# source_eagle.net
KiCad netlist of a schematic drawn in EAGLE
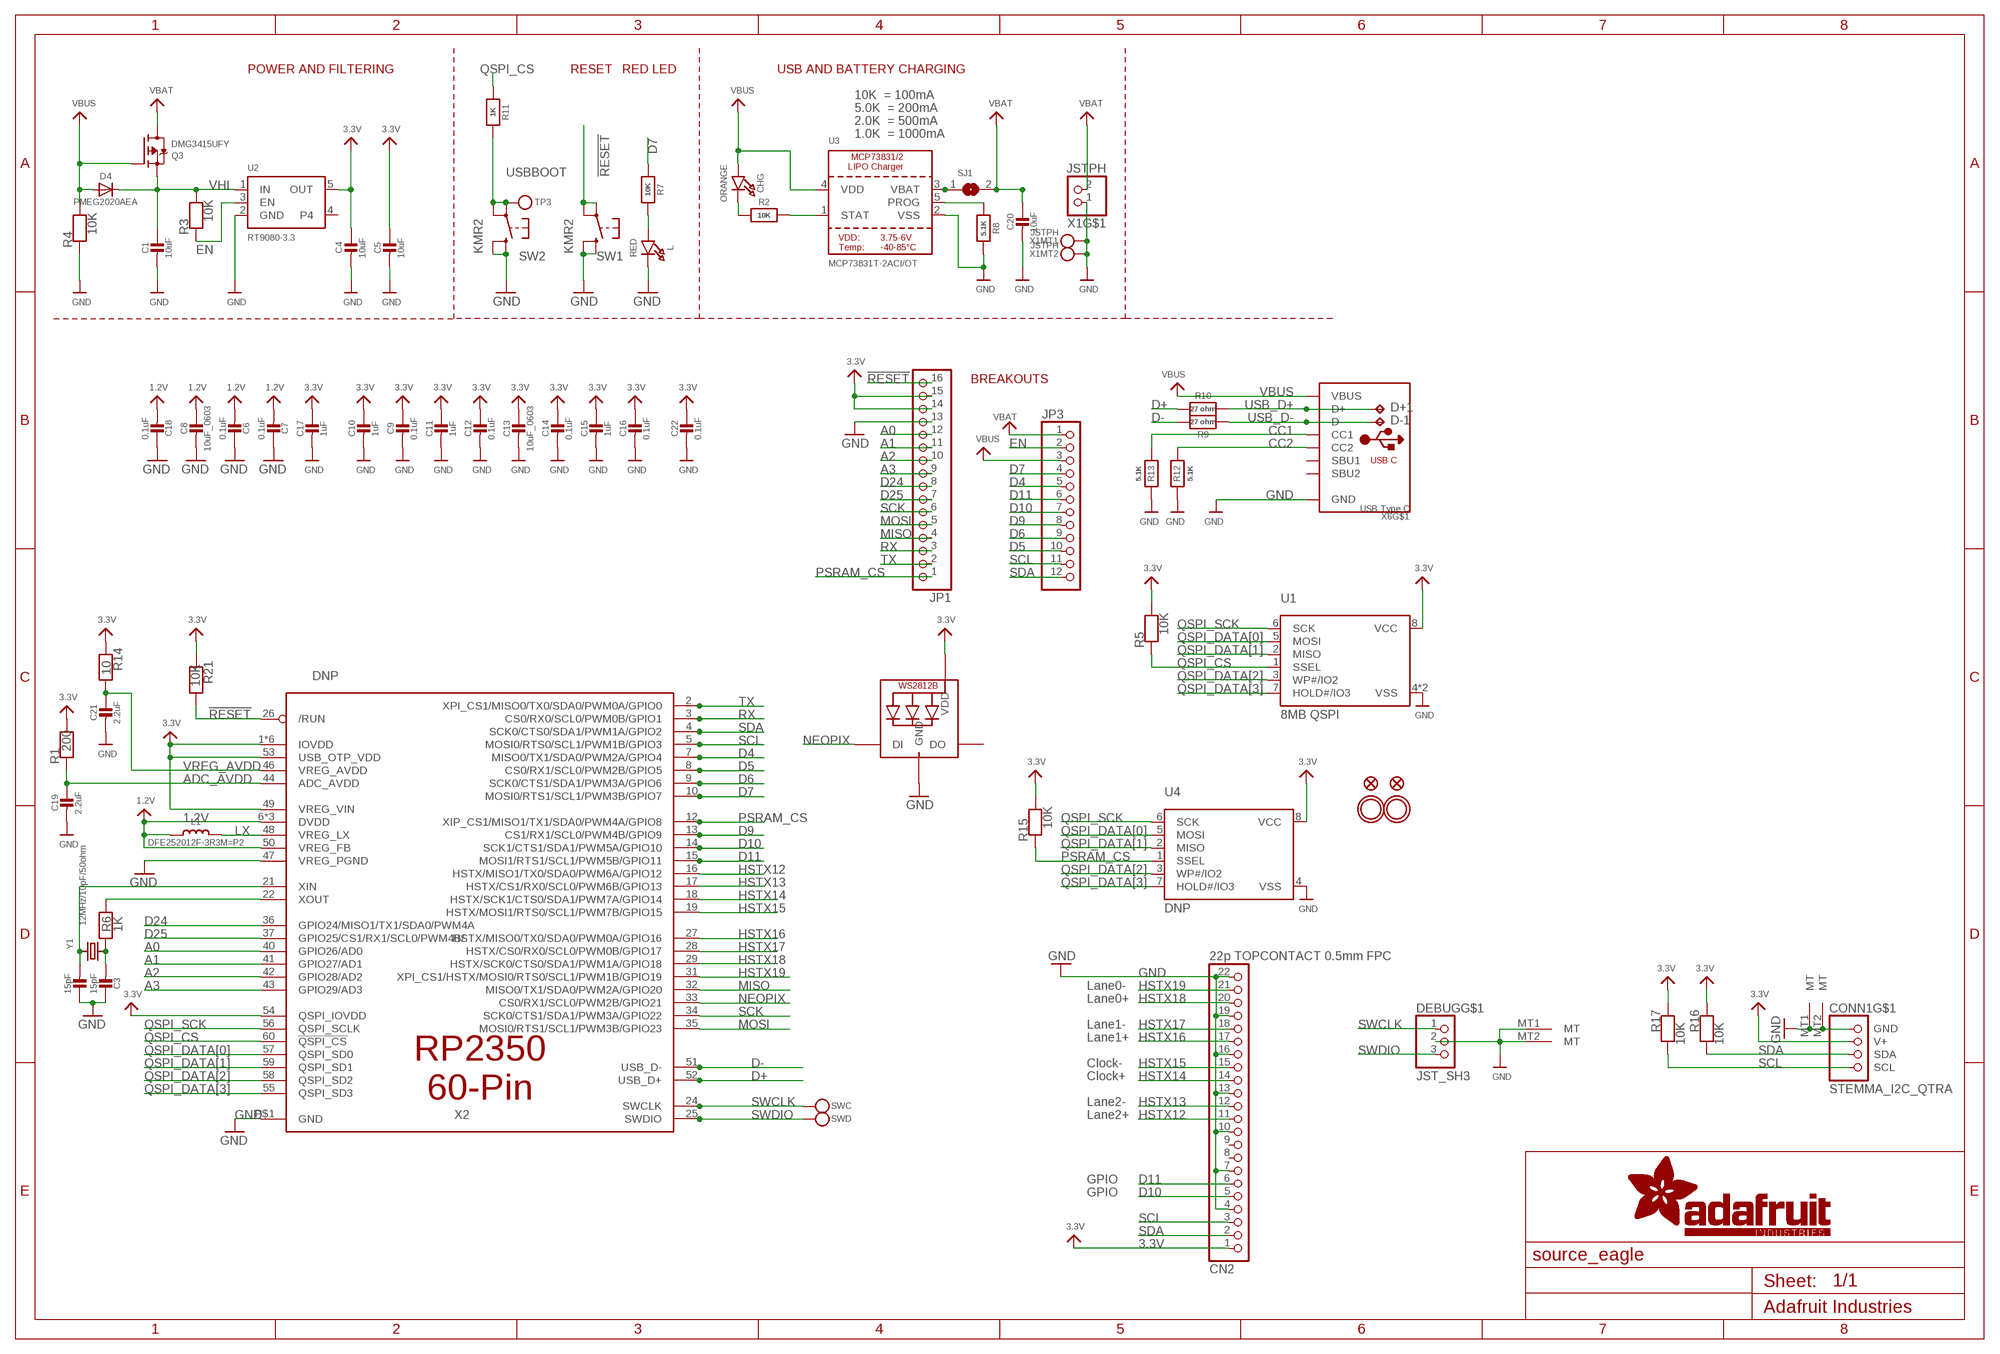
[diagram p0: schematic, sheet 1]

(export (version "E")
  (design (tool "Eeschema 10.0.6"))
  (components
    (comp (ref "C1")
      (value "10uF")
      (footprint "eagle-import:0805-NO")
      (libsource (lib "eagle-import") (part "CAP_CERAMIC0805-NOOUTLINE"))
    )
    (comp (ref "C2")
      (value "15pF")
      (footprint "eagle-import:_0402NO")
      (libsource (lib "eagle-import") (part "CAP_CERAMIC_0402NO"))
    )
    (comp (ref "C3")
      (value "15pF")
      (footprint "eagle-import:_0402NO")
      (libsource (lib "eagle-import") (part "CAP_CERAMIC_0402NO"))
    )
    (comp (ref "C4")
      (value "10uF")
      (footprint "eagle-import:0805-NO")
      (fields (field (name "REV") "B"))
      (libsource (lib "eagle-import") (part "CAP_CERAMIC0805-NOOUTLINE"))
    )
    (comp (ref "C5")
      (value "10uF")
      (footprint "eagle-import:0603-NO")
      (libsource (lib "eagle-import") (part "CAP_CERAMIC0603_NO"))
    )
    (comp (ref "C6")
      (value "0.1uF")
      (footprint "eagle-import:_0402NO")
      (libsource (lib "eagle-import") (part "CAP_CERAMIC_0402NO"))
    )
    (comp (ref "C7")
      (value "0.1uF")
      (footprint "eagle-import:_0402NO")
      (libsource (lib "eagle-import") (part "CAP_CERAMIC_0402NO"))
    )
    (comp (ref "C8")
      (value "10uF_0603")
      (footprint "eagle-import:_0603MP")
      (libsource (lib "eagle-import") (part "CAP_CERAMIC_0603MP"))
    )
    (comp (ref "C9")
      (value "0.1uF")
      (footprint "eagle-import:_0402NO")
      (libsource (lib "eagle-import") (part "CAP_CERAMIC_0402NO"))
    )
    (comp (ref "C10")
      (value "1uF")
      (footprint "eagle-import:_0402NO")
      (libsource (lib "eagle-import") (part "CAP_CERAMIC_0402NO"))
    )
    (comp (ref "C11")
      (value "1uF")
      (footprint "eagle-import:_0402NO")
      (libsource (lib "eagle-import") (part "CAP_CERAMIC_0402NO"))
    )
    (comp (ref "C12")
      (value "0.1uF")
      (footprint "eagle-import:_0402NO")
      (libsource (lib "eagle-import") (part "CAP_CERAMIC_0402NO"))
    )
    (comp (ref "C13")
      (value "10uF_0603")
      (footprint "eagle-import:_0603MP")
      (libsource (lib "eagle-import") (part "CAP_CERAMIC_0603MP"))
    )
    (comp (ref "C14")
      (value "0.1uF")
      (footprint "eagle-import:_0402NO")
      (libsource (lib "eagle-import") (part "CAP_CERAMIC_0402NO"))
    )
    (comp (ref "C15")
      (value "1uF")
      (footprint "eagle-import:_0402NO")
      (libsource (lib "eagle-import") (part "CAP_CERAMIC_0402NO"))
    )
    (comp (ref "C16")
      (value "0.1uF")
      (footprint "eagle-import:_0402NO")
      (libsource (lib "eagle-import") (part "CAP_CERAMIC_0402NO"))
    )
    (comp (ref "C17")
      (value "1uF")
      (footprint "eagle-import:_0402NO")
      (libsource (lib "eagle-import") (part "CAP_CERAMIC_0402NO"))
    )
    (comp (ref "C18")
      (value "0.1uF")
      (footprint "eagle-import:_0402NO")
      (libsource (lib "eagle-import") (part "CAP_CERAMIC_0402NO"))
    )
    (comp (ref "C19")
      (value "2.2uF")
      (footprint "eagle-import:_0402NO")
      (libsource (lib "eagle-import") (part "CAP_CERAMIC_0402NO"))
    )
    (comp (ref "C20")
      (value "10uF")
      (footprint "eagle-import:0805-NO")
      (libsource (lib "eagle-import") (part "CAP_CERAMIC0805-NOOUTLINE"))
    )
    (comp (ref "C21")
      (value "2.2uF")
      (footprint "eagle-import:_0402NO")
      (libsource (lib "eagle-import") (part "CAP_CERAMIC_0402NO"))
    )
    (comp (ref "C22")
      (value "0.1uF")
      (footprint "eagle-import:_0402NO")
      (libsource (lib "eagle-import") (part "CAP_CERAMIC_0402NO"))
    )
    (comp (ref "CHG")
      (value "ORANGE")
      (footprint "eagle-import:CHIPLED_0603_NOOUTLINE")
      (libsource (lib "eagle-import") (part "LED0603_NOOUTLINE"))
    )
    (comp (ref "CN2")
      (value "22p TOPCONTACT 0.5mm FPC")
      (footprint "eagle-import:FPC_22PIN")
      (libsource (lib "eagle-import") (part "HEADER-1X22_22PIN_0.5MM_BOT"))
    )
    (comp (ref "CONN1")
      (value "STEMMA_I2C_QTRA")
      (footprint "eagle-import:JST_SH4_RA")
      (libsource (lib "eagle-import") (part "STEMMA_I2C_QTRA"))
    )
    (comp (ref "D+1")
      (value "TPB1,27")
      (footprint "eagle-import:B1,27")
      (libsource (lib "eagle-import") (part "TPB1,27"))
    )
    (comp (ref "D-1")
      (value "TPB1,27")
      (footprint "eagle-import:B1,27")
      (libsource (lib "eagle-import") (part "TPB1,27"))
    )
    (comp (ref "D4")
      (value "PMEG2020AEA")
      (footprint "eagle-import:SOD-323F")
      (libsource (lib "eagle-import") (part "DIODESOD-323F"))
    )
    (comp (ref "DEBUG")
      (value "JST_SH3")
      (footprint "eagle-import:JST_SH3_RA")
      (libsource (lib "eagle-import") (part "CON_JST_SH_3PINVERT"))
    )
    (comp (ref "JP1")
      (value "HEADER-1X16ROUND")
      (footprint "eagle-import:1X16_ROUND")
      (libsource (lib "eagle-import") (part "HEADER-1X16ROUND"))
    )
    (comp (ref "JP3")
      (value "HEADER-1X12")
      (footprint "eagle-import:1X12_ROUND")
      (libsource (lib "eagle-import") (part "HEADER-1X12"))
    )
    (comp (ref "L")
      (value "RED")
      (footprint "eagle-import:CHIPLED_0603_NOOUTLINE")
      (libsource (lib "eagle-import") (part "LED0603_NOOUTLINE"))
    )
    (comp (ref "L1")
      (value "DFE252012F-3R3M=P2")
      (footprint "eagle-import:INDUCTOR_1007")
      (libsource (lib "eagle-import") (part "INDUCTOR"))
    )
    (comp (ref "LED1")
      (value "WS2812B_SK6805_1515")
      (footprint "eagle-import:SK6805_1515")
      (libsource (lib "eagle-import") (part "WS2812B_SK6805_1515"))
    )
    (comp (ref "Q3")
      (value "DMG3415UFY")
      (footprint "eagle-import:DFN2015-3")
      (libsource (lib "eagle-import") (part "MOSFET-P_DFN2015"))
    )
    (comp (ref "R1")
      (value "200")
      (footprint "eagle-import:_0402NO")
      (libsource (lib "eagle-import") (part "RESISTOR_0402NO"))
    )
    (comp (ref "R2")
      (value "10K")
      (footprint "eagle-import:_0402NO")
      (libsource (lib "eagle-import") (part "RESISTOR_0402NO"))
    )
    (comp (ref "R3")
      (value "10K")
      (footprint "eagle-import:_0402NO")
      (libsource (lib "eagle-import") (part "RESISTOR_0402NO"))
    )
    (comp (ref "R4")
      (value "10K")
      (footprint "eagle-import:_0402NO")
      (libsource (lib "eagle-import") (part "RESISTOR_0402NO"))
    )
    (comp (ref "R5")
      (value "10K")
      (footprint "eagle-import:_0402NO")
      (libsource (lib "eagle-import") (part "RESISTOR_0402NO"))
    )
    (comp (ref "R6")
      (value "1K")
      (footprint "eagle-import:_0402NO")
      (libsource (lib "eagle-import") (part "RESISTOR_0402NO"))
    )
    (comp (ref "R7")
      (value "10K")
      (footprint "eagle-import:_0402NO")
      (libsource (lib "eagle-import") (part "RESISTOR_0402NO"))
    )
    (comp (ref "R8")
      (value "5.1K")
      (footprint "eagle-import:_0402NO")
      (libsource (lib "eagle-import") (part "RESISTOR_0402NO"))
    )
    (comp (ref "R9")
      (value "27 ohm")
      (footprint "eagle-import:_0402NO")
      (libsource (lib "eagle-import") (part "RESISTOR_0402NO"))
    )
    (comp (ref "R10")
      (value "27 ohm")
      (footprint "eagle-import:_0402NO")
      (libsource (lib "eagle-import") (part "RESISTOR_0402NO"))
    )
    (comp (ref "R11")
      (value "1K")
      (footprint "eagle-import:_0402NO")
      (libsource (lib "eagle-import") (part "RESISTOR_0402NO"))
    )
    (comp (ref "R12")
      (value "5.1K")
      (footprint "eagle-import:_0402NO")
      (libsource (lib "eagle-import") (part "RESISTOR_0402NO"))
    )
    (comp (ref "R13")
      (value "5.1K")
      (footprint "eagle-import:_0402NO")
      (libsource (lib "eagle-import") (part "RESISTOR_0402NO"))
    )
    (comp (ref "R14")
      (value "10")
      (footprint "eagle-import:_0402NO")
      (libsource (lib "eagle-import") (part "RESISTOR_0402NO"))
    )
    (comp (ref "R15")
      (value "10K")
      (footprint "eagle-import:_0402NO")
      (libsource (lib "eagle-import") (part "RESISTOR_0402NO"))
    )
    (comp (ref "R16")
      (value "10K")
      (footprint "eagle-import:_0402NO")
      (libsource (lib "eagle-import") (part "RESISTOR_0402NO"))
    )
    (comp (ref "R17")
      (value "10K")
      (footprint "eagle-import:_0402NO")
      (libsource (lib "eagle-import") (part "RESISTOR_0402NO"))
    )
    (comp (ref "R21")
      (value "10K")
      (footprint "eagle-import:_0402NO")
      (libsource (lib "eagle-import") (part "RESISTOR_0402NO"))
    )
    (comp (ref "SJ1")
      (value "SOLDERJUMPERCLOSED")
      (footprint "eagle-import:SOLDERJUMPER_CLOSEDWIRE")
      (libsource (lib "eagle-import") (part "SOLDERJUMPERCLOSED"))
    )
    (comp (ref "SW1")
      (value "KMR2")
      (footprint "eagle-import:BTN_RKB2_4.6X2.8")
      (libsource (lib "eagle-import") (part "SWITCH_TACT_SMT_RKB2"))
    )
    (comp (ref "SW2")
      (value "KMR2")
      (footprint "eagle-import:BTN_RKB2_4.6X2.8")
      (libsource (lib "eagle-import") (part "SWITCH_TACT_SMT_RKB2"))
    )
    (comp (ref "SWC")
      (value "TESTPOINTROUND1MM")
      (footprint "eagle-import:TESTPOINT_ROUND_1MM")
      (libsource (lib "eagle-import") (part "TESTPOINTROUND1MM"))
    )
    (comp (ref "SWD")
      (value "TESTPOINTROUND1MM")
      (footprint "eagle-import:TESTPOINT_ROUND_1MM")
      (libsource (lib "eagle-import") (part "TESTPOINTROUND1MM"))
    )
    (comp (ref "TP3")
      (value "TESTPOINTROUND1.5MMNO")
      (footprint "eagle-import:TESTPOINT_ROUND_1.5MM_NO")
      (libsource (lib "eagle-import") (part "TESTPOINTROUND1.5MMNO"))
    )
    (comp (ref "U$31")
      (value "MOUNTINGHOLE2.5")
      (footprint "eagle-import:MOUNTINGHOLE_2.5_PLATED")
      (libsource (lib "eagle-import") (part "MOUNTINGHOLE2.5"))
    )
    (comp (ref "U$32")
      (value "MOUNTINGHOLE2.5")
      (footprint "eagle-import:MOUNTINGHOLE_2.5_PLATED")
      (libsource (lib "eagle-import") (part "MOUNTINGHOLE2.5"))
    )
    (comp (ref "U$34")
      (value "FIDUCIAL_1MM")
      (footprint "eagle-import:FIDUCIAL_1MM")
      (libsource (lib "eagle-import") (part "FIDUCIAL_1MM"))
    )
    (comp (ref "U$35")
      (value "FIDUCIAL_1MM")
      (footprint "eagle-import:FIDUCIAL_1MM")
      (libsource (lib "eagle-import") (part "FIDUCIAL_1MM"))
    )
    (comp (ref "U1")
      (value "8MB QSPI")
      (footprint "eagle-import:USON8_4X4")
      (libsource (lib "eagle-import") (part "SPIFLASH_8PIN_4X4"))
    )
    (comp (ref "U2")
      (value "RT9080-3.3")
      (footprint "eagle-import:SOT23-5")
      (fields (field (name "JLC_ROTATION") "0"))
      (libsource (lib "eagle-import") (part "VREG_SOT23-5"))
    )
    (comp (ref "U3")
      (value "MCP73831T-2ACI/OT")
      (footprint "eagle-import:SOT23-5")
      (libsource (lib "eagle-import") (part "MCP73831/2"))
    )
    (comp (ref "U4")
      (value "DNP")
      (footprint "eagle-import:SOIC8_150MIL")
      (libsource (lib "eagle-import") (part "SPIFLASH_8PIN"))
    )
    (comp (ref "X1")
      (value "JSTPH")
      (footprint "eagle-import:JSTPH2_BATT")
      (libsource (lib "eagle-import") (part "CON_JST_PH_2PIN_MT_BATT"))
    )
    (comp (ref "X2")
      (value "DNP")
      (footprint "eagle-import:QFN60_7MM_REDUCEDEPAD")
      (libsource (lib "eagle-import") (part "RP2350_QFN60"))
    )
    (comp (ref "X6")
      (value "USB Type C")
      (footprint "eagle-import:USB_C_CUSB31-CFM2AX-01-X")
      (libsource (lib "eagle-import") (part "USB_C"))
    )
    (comp (ref "Y1")
      (value "12MHz/10pF/50ohm")
      (footprint "eagle-import:CRYSTAL_2.5X2")
      (libsource (lib "eagle-import") (part "CRYSTAL2.5X2.0"))
    )
  )
  (nets
    (net (code "1") (name "/A0") (class "Default")
      (node (ref "JP1") (pin "12") (pinfunction "12_12") (pintype "passive"))
      (node (ref "X2") (pin "40") (pinfunction "GPIO26/AD0_40") (pintype "bidirectional"))
    )
    (net (code "2") (name "/A1") (class "Default")
      (node (ref "JP1") (pin "11") (pinfunction "11_11") (pintype "passive"))
      (node (ref "X2") (pin "41") (pinfunction "GPIO27/AD1_41") (pintype "bidirectional"))
    )
    (net (code "3") (name "/A2") (class "Default")
      (node (ref "JP1") (pin "10") (pinfunction "10_10") (pintype "passive"))
      (node (ref "X2") (pin "42") (pinfunction "GPIO28/AD2_42") (pintype "bidirectional"))
    )
    (net (code "4") (name "/A3") (class "Default")
      (node (ref "JP1") (pin "9") (pinfunction "9_9") (pintype "passive"))
      (node (ref "X2") (pin "43") (pinfunction "GPIO29/AD3_43") (pintype "bidirectional"))
    )
    (net (code "5") (name "/ADC_AVDD") (class "Default")
      (node (ref "C19") (pin "1") (pinfunction "1_1") (pintype "passive"))
      (node (ref "R1") (pin "1") (pinfunction "1_1") (pintype "passive"))
      (node (ref "X2") (pin "44") (pinfunction "ADC_AVDD_44") (pintype "power_in"))
    )
    (net (code "6") (name "/CC1") (class "Default")
      (node (ref "R13") (pin "2") (pinfunction "2_2") (pintype "passive"))
      (node (ref "X6") (pin "A5") (pinfunction "CC1_A5") (pintype "bidirectional"))
    )
    (net (code "7") (name "/CC2") (class "Default")
      (node (ref "R12") (pin "2") (pinfunction "2_2") (pintype "passive"))
      (node (ref "X6") (pin "B5") (pinfunction "CC2_B5") (pintype "bidirectional"))
    )
    (net (code "8") (name "/D+") (class "Default")
      (node (ref "R10") (pin "2") (pinfunction "2_2") (pintype "passive"))
      (node (ref "X2") (pin "52") (pinfunction "USB_D+_52") (pintype "bidirectional"))
    )
    (net (code "9") (name "/D-") (class "Default")
      (node (ref "R9") (pin "2") (pinfunction "2_2") (pintype "passive"))
      (node (ref "X2") (pin "51") (pinfunction "USB_D-_51") (pintype "bidirectional"))
    )
    (net (code "10") (name "/D4") (class "Default")
      (node (ref "JP3") (pin "5") (pinfunction "5_5") (pintype "passive"))
      (node (ref "X2") (pin "7") (pinfunction "MISO0/TX1/SDA0/PWM2A/GPIO4_7") (pintype "bidirectional"))
    )
    (net (code "11") (name "/D5") (class "Default")
      (node (ref "JP3") (pin "10") (pinfunction "10_10") (pintype "passive"))
      (node (ref "X2") (pin "8") (pinfunction "CS0/RX1/SCL0/PWM2B/GPIO5_8") (pintype "bidirectional"))
    )
    (net (code "12") (name "/D6") (class "Default")
      (node (ref "JP3") (pin "9") (pinfunction "9_9") (pintype "passive"))
      (node (ref "X2") (pin "9") (pinfunction "SCK0/CTS1/SDA1/PWM3A/GPIO6_9") (pintype "bidirectional"))
    )
    (net (code "13") (name "/D7") (class "Default")
      (node (ref "JP3") (pin "4") (pinfunction "4_4") (pintype "passive"))
      (node (ref "R7") (pin "1") (pinfunction "1_1") (pintype "passive"))
      (node (ref "X2") (pin "10") (pinfunction "MOSI0/RTS1/SCL1/PWM3B/GPIO7_10") (pintype "bidirectional"))
    )
    (net (code "14") (name "/D9") (class "Default")
      (node (ref "JP3") (pin "8") (pinfunction "8_8") (pintype "passive"))
      (node (ref "X2") (pin "13") (pinfunction "CS1/RX1/SCL0/PWM4B/GPIO9_13") (pintype "bidirectional"))
    )
    (net (code "15") (name "/D10") (class "Default")
      (node (ref "CN2") (pin "5") (pinfunction "5_5") (pintype "passive"))
      (node (ref "JP3") (pin "7") (pinfunction "7_7") (pintype "passive"))
      (node (ref "X2") (pin "14") (pinfunction "SCK1/CTS1/SDA1/PWM5A/GPIO10_14") (pintype "bidirectional"))
    )
    (net (code "16") (name "/D11") (class "Default")
      (node (ref "CN2") (pin "6") (pinfunction "6_6") (pintype "passive"))
      (node (ref "JP3") (pin "6") (pinfunction "6_6") (pintype "passive"))
      (node (ref "X2") (pin "15") (pinfunction "MOSI1/RTS1/SCL1/PWM5B/GPIO11_15") (pintype "bidirectional"))
    )
    (net (code "17") (name "/D24") (class "Default")
      (node (ref "JP1") (pin "8") (pinfunction "8_8") (pintype "passive"))
      (node (ref "X2") (pin "36") (pinfunction "GPIO24/MISO1/TX1/SDA0/PWM4A_36") (pintype "bidirectional"))
    )
    (net (code "18") (name "/D25") (class "Default")
      (node (ref "JP1") (pin "7") (pinfunction "7_7") (pintype "passive"))
      (node (ref "X2") (pin "37") (pinfunction "GPIO25/CS1/RX1/SCL0/PWM4B/_37") (pintype "bidirectional"))
    )
    (net (code "19") (name "/EN") (class "Default")
      (node (ref "JP3") (pin "2") (pinfunction "2_2") (pintype "passive"))
      (node (ref "R3") (pin "1") (pinfunction "1_1") (pintype "passive"))
      (node (ref "U2") (pin "3") (pinfunction "EN_3") (pintype "input"))
    )
    (net (code "20") (name "/HSTX12") (class "Default")
      (node (ref "CN2") (pin "11") (pinfunction "11_11") (pintype "passive"))
      (node (ref "X2") (pin "16") (pinfunction "HSTX/MISO1/TX0/SDA0/PWM6A/GPIO12_16") (pintype "bidirectional"))
    )
    (net (code "21") (name "/HSTX13") (class "Default")
      (node (ref "CN2") (pin "12") (pinfunction "12_12") (pintype "passive"))
      (node (ref "X2") (pin "17") (pinfunction "HSTX/CS1/RX0/SCL0/PWM6B/GPIO13_17") (pintype "bidirectional"))
    )
    (net (code "22") (name "/HSTX14") (class "Default")
      (node (ref "CN2") (pin "14") (pinfunction "14_14") (pintype "passive"))
      (node (ref "X2") (pin "18") (pinfunction "HSTX/SCK1/CTS0/SDA1/PWM7A/GPIO14_18") (pintype "bidirectional"))
    )
    (net (code "23") (name "/HSTX15") (class "Default")
      (node (ref "CN2") (pin "15") (pinfunction "15_15") (pintype "passive"))
      (node (ref "X2") (pin "19") (pinfunction "HSTX/MOSI1/RTS0/SCL1/PWM7B/GPIO15_19") (pintype "bidirectional"))
    )
    (net (code "24") (name "/HSTX16") (class "Default")
      (node (ref "CN2") (pin "17") (pinfunction "17_17") (pintype "passive"))
      (node (ref "X2") (pin "27") (pinfunction "HSTX/MISO0/TX0/SDA0/PWM0A/GPIO16_27") (pintype "bidirectional"))
    )
    (net (code "25") (name "/HSTX17") (class "Default")
      (node (ref "CN2") (pin "18") (pinfunction "18_18") (pintype "passive"))
      (node (ref "X2") (pin "28") (pinfunction "HSTX/CS0/RX0/SCL0/PWM0B/GPIO17_28") (pintype "bidirectional"))
    )
    (net (code "26") (name "/HSTX18") (class "Default")
      (node (ref "CN2") (pin "20") (pinfunction "20_20") (pintype "passive"))
      (node (ref "X2") (pin "29") (pinfunction "HSTX/SCK0/CTS0/SDA1/PWM1A/GPIO18_29") (pintype "bidirectional"))
    )
    (net (code "27") (name "/HSTX19") (class "Default")
      (node (ref "CN2") (pin "21") (pinfunction "21_21") (pintype "passive"))
      (node (ref "X2") (pin "31") (pinfunction "XPI_CS1/HSTX/MOSI0/RTS0/SCL1/PWM1B/GPIO19_31") (pintype "bidirectional"))
    )
    (net (code "28") (name "/LX") (class "Default")
      (node (ref "L1") (pin "P$2") (pinfunction "2_P$2") (pintype "passive"))
      (node (ref "X2") (pin "48") (pinfunction "VREG_LX_48") (pintype "input"))
    )
    (net (code "29") (name "/MISO") (class "Default")
      (node (ref "JP1") (pin "4") (pinfunction "4_4") (pintype "passive"))
      (node (ref "X2") (pin "32") (pinfunction "MISO0/TX1/SDA0/PWM2A/GPIO20_32") (pintype "bidirectional"))
    )
    (net (code "30") (name "/MOSI") (class "Default")
      (node (ref "JP1") (pin "5") (pinfunction "5_5") (pintype "passive"))
      (node (ref "X2") (pin "35") (pinfunction "MOSI0/RTS1/SCL1/PWM3B/GPIO23_35") (pintype "bidirectional"))
    )
    (net (code "31") (name "/NEOPIX") (class "Default")
      (node (ref "LED1") (pin "1") (pinfunction "DI_1") (pintype "input"))
      (node (ref "X2") (pin "33") (pinfunction "CS0/RX1/SCL0/PWM2B/GPIO21_33") (pintype "bidirectional"))
    )
    (net (code "32") (name "/PSRAM_CS") (class "Default")
      (node (ref "JP1") (pin "1") (pinfunction "1_1") (pintype "passive"))
      (node (ref "R15") (pin "1") (pinfunction "1_1") (pintype "passive"))
      (node (ref "U4") (pin "1") (pinfunction "SSEL_1") (pintype "bidirectional"))
      (node (ref "X2") (pin "12") (pinfunction "XIP_CS1/MISO1/TX1/SDA0/PWM4A/GPIO8_12") (pintype "bidirectional"))
    )
    (net (code "33") (name "/QSPI_CS") (class "Default")
      (node (ref "R11") (pin "1") (pinfunction "1_1") (pintype "passive"))
      (node (ref "R5") (pin "1") (pinfunction "1_1") (pintype "passive"))
      (node (ref "U1") (pin "1") (pinfunction "SSEL_1") (pintype "bidirectional"))
      (node (ref "X2") (pin "60") (pinfunction "~{QSPI_CS}_60") (pintype "bidirectional"))
    )
    (net (code "34") (name "/QSPI_DATA[0]") (class "Default")
      (node (ref "U1") (pin "5") (pinfunction "MOSI_5") (pintype "bidirectional"))
      (node (ref "U4") (pin "5") (pinfunction "MOSI_5") (pintype "bidirectional"))
      (node (ref "X2") (pin "57") (pinfunction "QSPI_SD0_57") (pintype "bidirectional"))
    )
    (net (code "35") (name "/QSPI_DATA[1]") (class "Default")
      (node (ref "U1") (pin "2") (pinfunction "MISO_2") (pintype "bidirectional"))
      (node (ref "U4") (pin "2") (pinfunction "MISO_2") (pintype "bidirectional"))
      (node (ref "X2") (pin "59") (pinfunction "QSPI_SD1_59") (pintype "bidirectional"))
    )
    (net (code "36") (name "/QSPI_DATA[2]") (class "Default")
      (node (ref "U1") (pin "3") (pinfunction "WP#/IO2_3") (pintype "bidirectional"))
      (node (ref "U4") (pin "3") (pinfunction "WP#/IO2_3") (pintype "bidirectional"))
      (node (ref "X2") (pin "58") (pinfunction "QSPI_SD2_58") (pintype "bidirectional"))
    )
    (net (code "37") (name "/QSPI_DATA[3]") (class "Default")
      (node (ref "U1") (pin "7") (pinfunction "HOLD#/IO3_7") (pintype "bidirectional"))
      (node (ref "U4") (pin "7") (pinfunction "HOLD#/IO3_7") (pintype "bidirectional"))
      (node (ref "X2") (pin "55") (pinfunction "QSPI_SD3_55") (pintype "bidirectional"))
    )
    (net (code "38") (name "/QSPI_SCK") (class "Default")
      (node (ref "U1") (pin "6") (pinfunction "SCK_6") (pintype "bidirectional"))
      (node (ref "U4") (pin "6") (pinfunction "SCK_6") (pintype "bidirectional"))
      (node (ref "X2") (pin "56") (pinfunction "QSPI_SCLK_56") (pintype "bidirectional"))
    )
    (net (code "39") (name "/RX") (class "Default")
      (node (ref "JP1") (pin "3") (pinfunction "3_3") (pintype "passive"))
      (node (ref "X2") (pin "3") (pinfunction "CS0/RX0/SCL0/PWM0B/GPIO1_3") (pintype "bidirectional"))
    )
    (net (code "40") (name "/SCK") (class "Default")
      (node (ref "JP1") (pin "6") (pinfunction "6_6") (pintype "passive"))
      (node (ref "X2") (pin "34") (pinfunction "SCK0/CTS1/SDA1/PWM3A/GPIO22_34") (pintype "bidirectional"))
    )
    (net (code "41") (name "/SCL") (class "Default")
      (node (ref "CN2") (pin "3") (pinfunction "3_3") (pintype "passive"))
      (node (ref "CONN1") (pin "4") (pinfunction "SCL_4") (pintype "passive"))
      (node (ref "JP3") (pin "11") (pinfunction "11_11") (pintype "passive"))
      (node (ref "R17") (pin "2") (pinfunction "2_2") (pintype "passive"))
      (node (ref "X2") (pin "5") (pinfunction "MOSI0/RTS0/SCL1/PWM1B/GPIO3_5") (pintype "bidirectional"))
    )
    (net (code "42") (name "/SDA") (class "Default")
      (node (ref "CN2") (pin "2") (pinfunction "2_2") (pintype "passive"))
      (node (ref "CONN1") (pin "3") (pinfunction "SDA_3") (pintype "passive"))
      (node (ref "JP3") (pin "12") (pinfunction "12_12") (pintype "passive"))
      (node (ref "R16") (pin "2") (pinfunction "2_2") (pintype "passive"))
      (node (ref "X2") (pin "4") (pinfunction "SCK0/CTS0/SDA1/PWM1A/GPIO2_4") (pintype "bidirectional"))
    )
    (net (code "43") (name "/SWCLK") (class "Default")
      (node (ref "DEBUG") (pin "1") (pinfunction "1_1") (pintype "passive"))
      (node (ref "SWC") (pin "P$1") (pinfunction "P$1_P$1") (pintype "bidirectional"))
      (node (ref "X2") (pin "24") (pinfunction "SWCLK_24") (pintype "bidirectional"))
    )
    (net (code "44") (name "/SWDIO") (class "Default")
      (node (ref "DEBUG") (pin "3") (pinfunction "3_3") (pintype "passive"))
      (node (ref "SWD") (pin "P$1") (pinfunction "P$1_P$1") (pintype "bidirectional"))
      (node (ref "X2") (pin "25") (pinfunction "SWDIO_25") (pintype "bidirectional"))
    )
    (net (code "45") (name "/TX") (class "Default")
      (node (ref "JP1") (pin "2") (pinfunction "2_2") (pintype "passive"))
      (node (ref "X2") (pin "2") (pinfunction "XPI_CS1/MISO0/TX0/SDA0/PWM0A/GPIO0_2") (pintype "bidirectional"))
    )
    (net (code "46") (name "/USBBOOT") (class "Default")
      (node (ref "R11") (pin "2") (pinfunction "2_2") (pintype "passive"))
      (node (ref "SW2") (pin "A") (pinfunction "P_A") (pintype "passive"))
      (node (ref "SW2") (pin "A'") (pinfunction "P1_A'") (pintype "passive"))
      (node (ref "TP3") (pin "P$1") (pinfunction "P$1_P$1") (pintype "bidirectional"))
    )
    (net (code "47") (name "/USB_D+") (class "Default")
      (node (ref "D+1") (pin "TP") (pinfunction "TP_TP") (pintype "input"))
      (node (ref "R10") (pin "1") (pinfunction "1_1") (pintype "passive"))
      (node (ref "X6") (pin "A6") (pinfunction "D+_A6") (pintype "bidirectional"))
      (node (ref "X6") (pin "B6") (pinfunction "D+_B6") (pintype "bidirectional"))
    )
    (net (code "48") (name "/USB_D-") (class "Default")
      (node (ref "D-1") (pin "TP") (pinfunction "TP_TP") (pintype "input"))
      (node (ref "R9") (pin "1") (pinfunction "1_1") (pintype "passive"))
      (node (ref "X6") (pin "A7") (pinfunction "D-_A7") (pintype "bidirectional"))
      (node (ref "X6") (pin "B7") (pinfunction "D-_B7") (pintype "bidirectional"))
    )
    (net (code "49") (name "/VHI") (class "Default")
      (node (ref "C1") (pin "1") (pinfunction "1_1") (pintype "passive"))
      (node (ref "D4") (pin "C") (pinfunction "C_C") (pintype "passive"))
      (node (ref "Q3") (pin "2") (pinfunction "S_2") (pintype "passive"))
      (node (ref "R3") (pin "2") (pinfunction "2_2") (pintype "passive"))
      (node (ref "U2") (pin "1") (pinfunction "IN_1") (pintype "power_in"))
    )
    (net (code "50") (name "/VREG_AVDD") (class "Default")
      (node (ref "C21") (pin "1") (pinfunction "1_1") (pintype "passive"))
      (node (ref "R14") (pin "2") (pinfunction "2_2") (pintype "passive"))
      (node (ref "X2") (pin "46") (pinfunction "VREG_AVDD_46") (pintype "power_in"))
    )
    (net (code "51") (name "/~{RESET}") (class "Default")
      (node (ref "JP1") (pin "16") (pinfunction "16_16") (pintype "passive"))
      (node (ref "R21") (pin "2") (pinfunction "2_2") (pintype "passive"))
      (node (ref "SW1") (pin "A") (pinfunction "P_A") (pintype "passive"))
      (node (ref "SW1") (pin "A'") (pinfunction "P1_A'") (pintype "passive"))
      (node (ref "X2") (pin "26") (pinfunction "/RUN_26") (pintype "bidirectional"))
    )
    (net (code "52") (name "1.2V") (class "Default")
      (node (ref "C18") (pin "2") (pinfunction "2_2") (pintype "passive"))
      (node (ref "C6") (pin "2") (pinfunction "2_2") (pintype "passive"))
      (node (ref "C7") (pin "2") (pinfunction "2_2") (pintype "passive"))
      (node (ref "C8") (pin "1") (pinfunction "1_1") (pintype "passive"))
      (node (ref "L1") (pin "P$1") (pinfunction "1_P$1") (pintype "passive"))
      (node (ref "X2") (pin "23") (pinfunction "DVDD_23") (pintype "power_in"))
      (node (ref "X2") (pin "39") (pinfunction "DVDD_39") (pintype "power_in"))
      (node (ref "X2") (pin "50") (pinfunction "VREG_FB_50") (pintype "input"))
      (node (ref "X2") (pin "6") (pinfunction "DVDD_6") (pintype "power_in"))
    )
    (net (code "53") (name "3.3V") (class "Default")
      (node (ref "C10") (pin "1") (pinfunction "1_1") (pintype "passive"))
      (node (ref "C11") (pin "1") (pinfunction "1_1") (pintype "passive"))
      (node (ref "C12") (pin "1") (pinfunction "1_1") (pintype "passive"))
      (node (ref "C13") (pin "1") (pinfunction "1_1") (pintype "passive"))
      (node (ref "C14") (pin "1") (pinfunction "1_1") (pintype "passive"))
      (node (ref "C15") (pin "1") (pinfunction "1_1") (pintype "passive"))
      (node (ref "C16") (pin "1") (pinfunction "1_1") (pintype "passive"))
      (node (ref "C17") (pin "1") (pinfunction "1_1") (pintype "passive"))
      (node (ref "C22") (pin "1") (pinfunction "1_1") (pintype "passive"))
      (node (ref "C4") (pin "1") (pinfunction "1_1") (pintype "passive"))
      (node (ref "C5") (pin "1") (pinfunction "1_1") (pintype "passive"))
      (node (ref "C9") (pin "1") (pinfunction "1_1") (pintype "passive"))
      (node (ref "CN2") (pin "1") (pinfunction "1_1") (pintype "passive"))
      (node (ref "CONN1") (pin "2") (pinfunction "V+_2") (pintype "passive"))
      (node (ref "JP1") (pin "14") (pinfunction "14_14") (pintype "passive"))
      (node (ref "JP1") (pin "15") (pinfunction "15_15") (pintype "passive"))
      (node (ref "LED1") (pin "2") (pinfunction "VDD_2") (pintype "power_in"))
      (node (ref "R1") (pin "2") (pinfunction "2_2") (pintype "passive"))
      (node (ref "R14") (pin "1") (pinfunction "1_1") (pintype "passive"))
      (node (ref "R15") (pin "2") (pinfunction "2_2") (pintype "passive"))
      (node (ref "R16") (pin "1") (pinfunction "1_1") (pintype "passive"))
      (node (ref "R17") (pin "1") (pinfunction "1_1") (pintype "passive"))
      (node (ref "R21") (pin "1") (pinfunction "1_1") (pintype "passive"))
      (node (ref "R5") (pin "2") (pinfunction "2_2") (pintype "passive"))
      (node (ref "U1") (pin "8") (pinfunction "VCC_8") (pintype "bidirectional"))
      (node (ref "U2") (pin "5") (pinfunction "OUT_5") (pintype "power_in"))
      (node (ref "U4") (pin "8") (pinfunction "VCC_8") (pintype "bidirectional"))
      (node (ref "X2") (pin "1") (pinfunction "IOVDD_1") (pintype "power_in"))
      (node (ref "X2") (pin "11") (pinfunction "IOVDD_11") (pintype "power_in"))
      (node (ref "X2") (pin "20") (pinfunction "IOVDD_20") (pintype "power_in"))
      (node (ref "X2") (pin "30") (pinfunction "IOVDD_30") (pintype "power_in"))
      (node (ref "X2") (pin "38") (pinfunction "IOVDD_38") (pintype "power_in"))
      (node (ref "X2") (pin "45") (pinfunction "IOVDD_45") (pintype "power_in"))
      (node (ref "X2") (pin "49") (pinfunction "VREG_VIN_49") (pintype "input"))
      (node (ref "X2") (pin "53") (pinfunction "USB_OTP_VDD_53") (pintype "power_in"))
      (node (ref "X2") (pin "54") (pinfunction "QSPI_IOVDD_54") (pintype "power_in"))
    )
    (net (code "54") (name "GND") (class "Default")
      (node (ref "C1") (pin "2") (pinfunction "2_2") (pintype "passive"))
      (node (ref "C10") (pin "2") (pinfunction "2_2") (pintype "passive"))
      (node (ref "C11") (pin "2") (pinfunction "2_2") (pintype "passive"))
      (node (ref "C12") (pin "2") (pinfunction "2_2") (pintype "passive"))
      (node (ref "C13") (pin "2") (pinfunction "2_2") (pintype "passive"))
      (node (ref "C14") (pin "2") (pinfunction "2_2") (pintype "passive"))
      (node (ref "C15") (pin "2") (pinfunction "2_2") (pintype "passive"))
      (node (ref "C16") (pin "2") (pinfunction "2_2") (pintype "passive"))
      (node (ref "C17") (pin "2") (pinfunction "2_2") (pintype "passive"))
      (node (ref "C18") (pin "1") (pinfunction "1_1") (pintype "passive"))
      (node (ref "C19") (pin "2") (pinfunction "2_2") (pintype "passive"))
      (node (ref "C2") (pin "1") (pinfunction "1_1") (pintype "passive"))
      (node (ref "C20") (pin "2") (pinfunction "2_2") (pintype "passive"))
      (node (ref "C21") (pin "2") (pinfunction "2_2") (pintype "passive"))
      (node (ref "C22") (pin "2") (pinfunction "2_2") (pintype "passive"))
      (node (ref "C3") (pin "1") (pinfunction "1_1") (pintype "passive"))
      (node (ref "C4") (pin "2") (pinfunction "2_2") (pintype "passive"))
      (node (ref "C5") (pin "2") (pinfunction "2_2") (pintype "passive"))
      (node (ref "C6") (pin "1") (pinfunction "1_1") (pintype "passive"))
      (node (ref "C7") (pin "1") (pinfunction "1_1") (pintype "passive"))
      (node (ref "C8") (pin "2") (pinfunction "2_2") (pintype "passive"))
      (node (ref "C9") (pin "2") (pinfunction "2_2") (pintype "passive"))
      (node (ref "CN2") (pin "10") (pinfunction "10_10") (pintype "passive"))
      (node (ref "CN2") (pin "13") (pinfunction "13_13") (pintype "passive"))
      (node (ref "CN2") (pin "16") (pinfunction "16_16") (pintype "passive"))
      (node (ref "CN2") (pin "19") (pinfunction "19_19") (pintype "passive"))
      (node (ref "CN2") (pin "22") (pinfunction "22_22") (pintype "passive"))
      (node (ref "CN2") (pin "4") (pinfunction "4_4") (pintype "passive"))
      (node (ref "CN2") (pin "7") (pinfunction "7_7") (pintype "passive"))
      (node (ref "CONN1") (pin "1") (pinfunction "GND_1") (pintype "passive"))
      (node (ref "CONN1") (pin "MT1") (pinfunction "MT_MT1") (pintype "bidirectional"))
      (node (ref "CONN1") (pin "MT2") (pinfunction "MT_MT2") (pintype "bidirectional"))
      (node (ref "DEBUG") (pin "2") (pinfunction "2_2") (pintype "passive"))
      (node (ref "DEBUG") (pin "MT1") (pinfunction "MT_MT1") (pintype "bidirectional"))
      (node (ref "DEBUG") (pin "MT2") (pinfunction "MT_MT2") (pintype "bidirectional"))
      (node (ref "JP1") (pin "13") (pinfunction "13_13") (pintype "passive"))
      (node (ref "L") (pin "C") (pinfunction "C_C") (pintype "passive"))
      (node (ref "LED1") (pin "4") (pinfunction "GND_4") (pintype "power_in"))
      (node (ref "R12") (pin "1") (pinfunction "1_1") (pintype "passive"))
      (node (ref "R13") (pin "1") (pinfunction "1_1") (pintype "passive"))
      (node (ref "R4") (pin "1") (pinfunction "1_1") (pintype "passive"))
      (node (ref "R8") (pin "2") (pinfunction "2_2") (pintype "passive"))
      (node (ref "SW1") (pin "B") (pinfunction "S_B") (pintype "passive"))
      (node (ref "SW1") (pin "B'") (pinfunction "S1_B'") (pintype "passive"))
      (node (ref "SW2") (pin "B") (pinfunction "S_B") (pintype "passive"))
      (node (ref "SW2") (pin "B'") (pinfunction "S1_B'") (pintype "passive"))
      (node (ref "U1") (pin "4") (pinfunction "VSS_4") (pintype "bidirectional"))
      (node (ref "U1") (pin "PAD") (pinfunction "VSS_PAD") (pintype "bidirectional"))
      (node (ref "U2") (pin "2") (pinfunction "GND_2") (pintype "power_in"))
      (node (ref "U3") (pin "2") (pinfunction "VSS_2") (pintype "power_in"))
      (node (ref "U4") (pin "4") (pinfunction "VSS_4") (pintype "bidirectional"))
      (node (ref "X1") (pin "1") (pinfunction "1_1") (pintype "passive"))
      (node (ref "X1") (pin "NC1") (pinfunction "P$1_NC1") (pintype "bidirectional"))
      (node (ref "X1") (pin "NC2") (pinfunction "P$1_NC2") (pintype "bidirectional"))
      (node (ref "X2") (pin "47") (pinfunction "VREG_PGND_47") (pintype "power_in"))
      (node (ref "X2") (pin "P$1") (pinfunction "GND_P$1") (pintype "power_in"))
      (node (ref "X6") (pin "A1B12") (pinfunction "GND_A1B12") (pintype "power_in"))
      (node (ref "X6") (pin "B1A12") (pinfunction "GND_B1A12") (pintype "power_in"))
    )
    (net (code "55") (name "Net-(C3-Pad2)") (class "Default")
      (node (ref "C3") (pin "2") (pinfunction "2_2") (pintype "passive"))
      (node (ref "R6") (pin "1") (pinfunction "1_1") (pintype "passive"))
      (node (ref "Y1") (pin "1") (pinfunction "1_1") (pintype "passive"))
    )
    (net (code "56") (name "Net-(CHG-PadC)") (class "Default")
      (node (ref "CHG") (pin "C") (pinfunction "C_C") (pintype "passive"))
      (node (ref "R2") (pin "1") (pinfunction "1_1") (pintype "passive"))
    )
    (net (code "57") (name "Net-(L-PadA)") (class "Default")
      (node (ref "L") (pin "A") (pinfunction "A_A") (pintype "passive"))
      (node (ref "R7") (pin "2") (pinfunction "2_2") (pintype "passive"))
    )
    (net (code "58") (name "Net-(U3-PROG)") (class "Default")
      (node (ref "R8") (pin "1") (pinfunction "1_1") (pintype "passive"))
      (node (ref "U3") (pin "5") (pinfunction "PROG_5") (pintype "input"))
    )
    (net (code "59") (name "Net-(U3-STAT)") (class "Default")
      (node (ref "R2") (pin "2") (pinfunction "2_2") (pintype "passive"))
      (node (ref "U3") (pin "1") (pinfunction "STAT_1") (pintype "output"))
    )
    (net (code "60") (name "Net-(U3-VBAT)") (class "Default")
      (node (ref "SJ1") (pin "1") (pinfunction "1_1") (pintype "passive"))
      (node (ref "U3") (pin "3") (pinfunction "VBAT_3") (pintype "power_in"))
    )
    (net (code "61") (name "Net-(X2-XIN)") (class "Default")
      (node (ref "C2") (pin "2") (pinfunction "2_2") (pintype "passive"))
      (node (ref "X2") (pin "21") (pinfunction "XIN_21") (pintype "input"))
      (node (ref "Y1") (pin "3") (pinfunction "2_3") (pintype "passive"))
    )
    (net (code "62") (name "Net-(X2-XOUT)") (class "Default")
      (node (ref "R6") (pin "2") (pinfunction "2_2") (pintype "passive"))
      (node (ref "X2") (pin "22") (pinfunction "XOUT_22") (pintype "output"))
    )
    (net (code "63") (name "VBAT") (class "Default")
      (node (ref "C20") (pin "1") (pinfunction "1_1") (pintype "passive"))
      (node (ref "JP3") (pin "1") (pinfunction "1_1") (pintype "passive"))
      (node (ref "Q3") (pin "3") (pinfunction "D_3") (pintype "passive"))
      (node (ref "SJ1") (pin "2") (pinfunction "2_2") (pintype "passive"))
      (node (ref "X1") (pin "2") (pinfunction "2_2") (pintype "passive"))
    )
    (net (code "64") (name "VBUS") (class "Default")
      (node (ref "CHG") (pin "A") (pinfunction "A_A") (pintype "passive"))
      (node (ref "D4") (pin "A") (pinfunction "A_A") (pintype "passive"))
      (node (ref "JP3") (pin "3") (pinfunction "3_3") (pintype "passive"))
      (node (ref "Q3") (pin "1") (pinfunction "G_1") (pintype "passive"))
      (node (ref "R4") (pin "2") (pinfunction "2_2") (pintype "passive"))
      (node (ref "U3") (pin "4") (pinfunction "VDD_4") (pintype "power_in"))
      (node (ref "X6") (pin "A4B9") (pinfunction "VBUS_A4B9") (pintype "power_in"))
      (node (ref "X6") (pin "B4A9") (pinfunction "VBUS_B4A9") (pintype "power_in"))
    )
    (net (code "65") (name "unconnected-(CN2-Pad8)") (class "Default")
      (node (ref "CN2") (pin "8") (pinfunction "8_8") (pintype "passive"))
    )
    (net (code "66") (name "unconnected-(CN2-Pad9)") (class "Default")
      (node (ref "CN2") (pin "9") (pinfunction "9_9") (pintype "passive"))
    )
    (net (code "67") (name "unconnected-(LED1-DO-Pad3)") (class "Default")
      (node (ref "LED1") (pin "3") (pinfunction "DO_3") (pintype "output"))
    )
    (net (code "68") (name "unconnected-(U2-P4-Pad4)") (class "Default")
      (node (ref "U2") (pin "4") (pinfunction "P4_4") (pintype "bidirectional"))
    )
    (net (code "69") (name "unconnected-(X6A-SBU1-PadA8)") (class "Default")
      (node (ref "X6") (pin "A8") (pinfunction "SBU1_A8") (pintype "bidirectional"))
    )
    (net (code "70") (name "unconnected-(X6A-SBU2-PadB8)") (class "Default")
      (node (ref "X6") (pin "B8") (pinfunction "SBU2_B8") (pintype "bidirectional"))
    )
  )
)
